# SCH_Display-LCD_Altium.net
KiCad netlist of a schematic drawn in Altium Designer
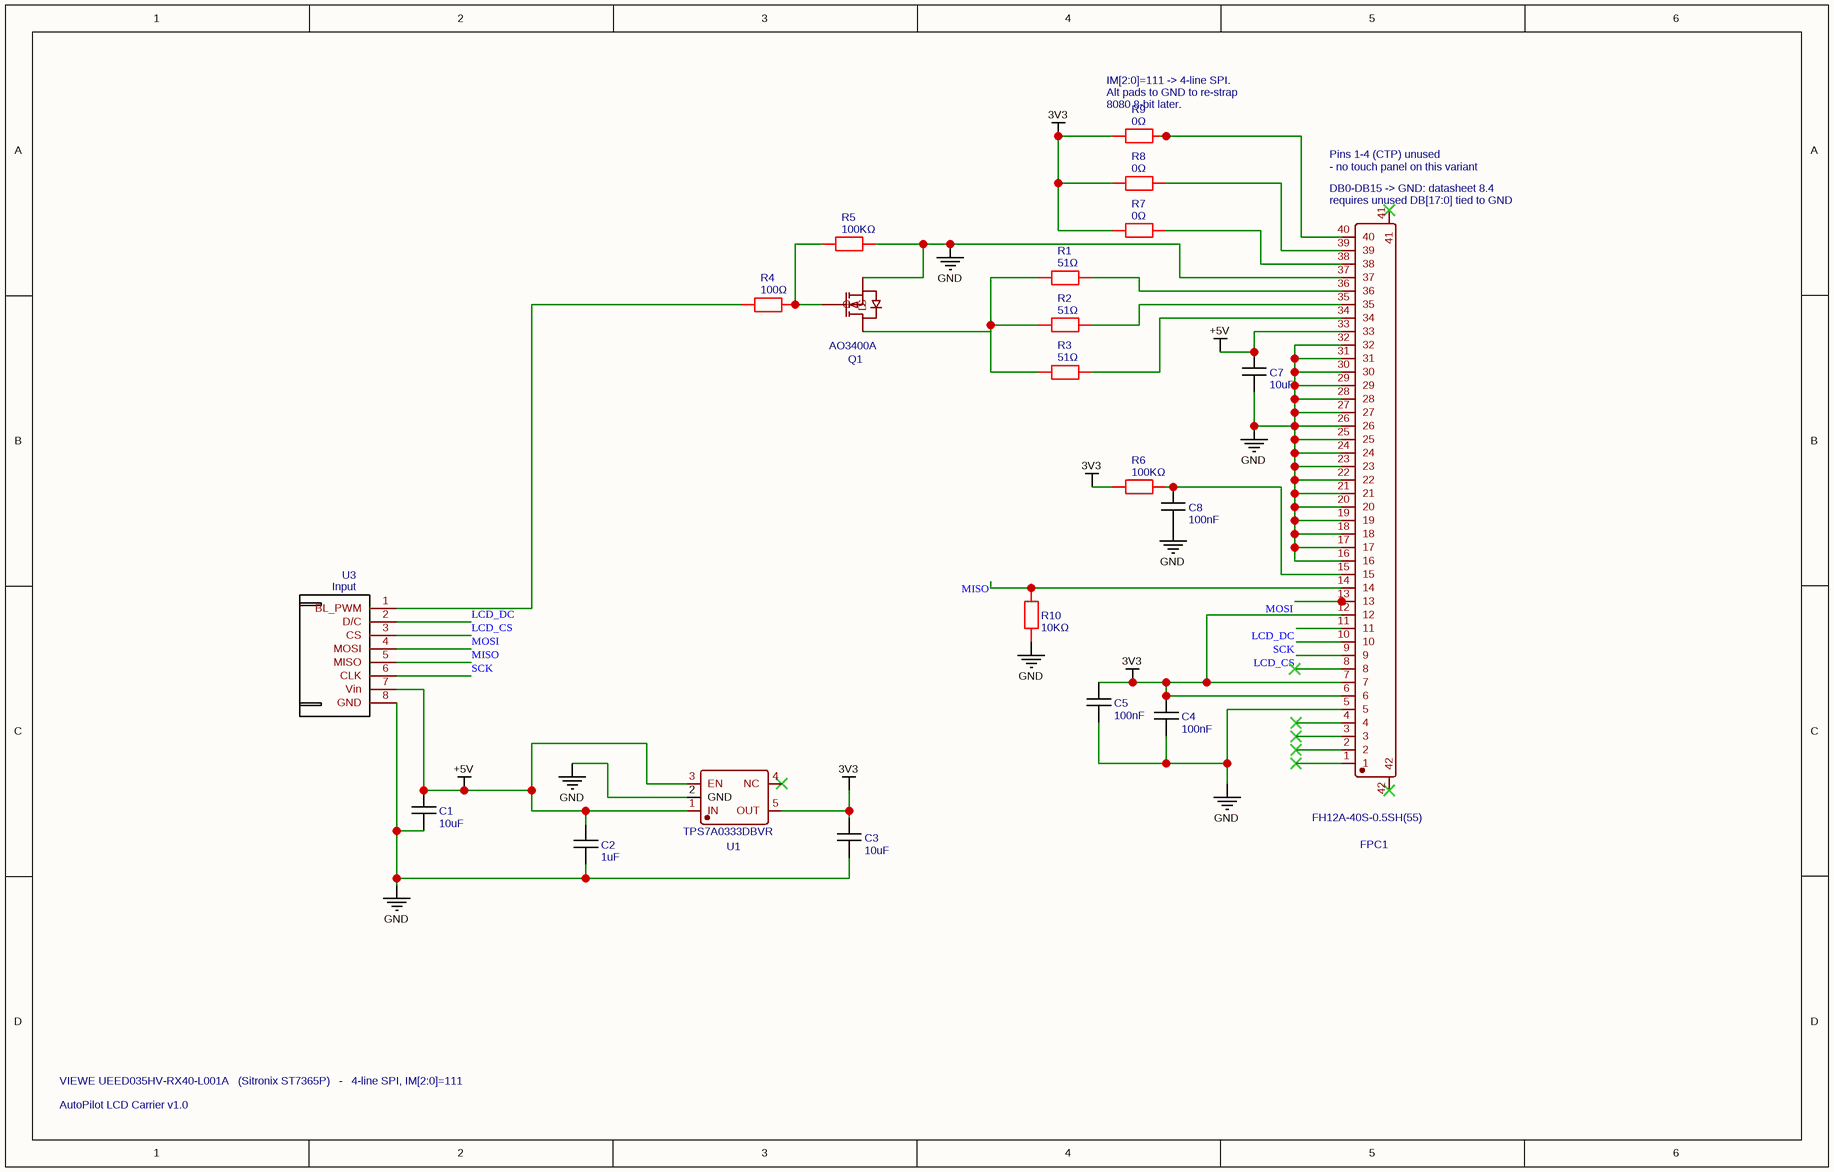
[diagram p0: SCH_Display-LCD_Altium.schdoc]

(export (version "E")
  (design (tool "Eeschema 10.0.6"))
  (components
    (comp (ref "C1")
      (value "10uF")
      (fields
        (field (name "MANUFACTURER PART") "Capacitor_Ceramic")
        (field (name "CONTRIBUTOR") "huuvinhz755")
      )
      (libsource (lib "altium-import") (part "root_3_10uF_"))
    )
    (comp (ref "C2")
      (value "1uF")
      (fields
        (field (name "MANUFACTURER PART") "Capacitor_Ceramic")
        (field (name "CONTRIBUTOR") "huuvinhz755")
      )
      (libsource (lib "altium-import") (part "root_3_1uF_"))
    )
    (comp (ref "C3")
      (value "10uF")
      (fields
        (field (name "MANUFACTURER PART") "Capacitor_Ceramic")
        (field (name "CONTRIBUTOR") "huuvinhz755")
      )
      (libsource (lib "altium-import") (part "root_3_10uF_"))
    )
    (comp (ref "C4")
      (value "100nF")
      (fields
        (field (name "MANUFACTURER PART") "Capacitor_Ceramic")
        (field (name "CONTRIBUTOR") "huuvinhz755")
      )
      (libsource (lib "altium-import") (part "root_3_100nF_"))
    )
    (comp (ref "C5")
      (value "100nF")
      (fields
        (field (name "MANUFACTURER PART") "Capacitor_Ceramic")
        (field (name "CONTRIBUTOR") "huuvinhz755")
      )
      (libsource (lib "altium-import") (part "root_3_100nF_"))
    )
    (comp (ref "C7")
      (value "10uF")
      (fields
        (field (name "MANUFACTURER PART") "Capacitor_Ceramic")
        (field (name "CONTRIBUTOR") "huuvinhz755")
      )
      (libsource (lib "altium-import") (part "root_3_10uF_"))
    )
    (comp (ref "C8")
      (value "100nF")
      (fields
        (field (name "MANUFACTURER PART") "Capacitor_Ceramic")
        (field (name "CONTRIBUTOR") "huuvinhz755")
      )
      (libsource (lib "altium-import") (part "root_3_100nF_"))
    )
    (comp (ref "FPC1")
      (value "FH12A-40S-0.5SH(55)")
      (fields (field (name "MANUFACTURER") "HRS(广濑)") (field (name "CONTRIBUTOR") "LCSC"))
      (libsource (lib "altium-import") (part "root_0_FH12A-40S-0.5SH(55)_"))
    )
    (comp (ref "Q1")
      (value "AO3400A")
      (fields (field (name "MANUFACTURER") "AOS"))
      (libsource (lib "altium-import") (part "root_0_AO3400A_"))
    )
    (comp (ref "R1")
      (value "51Ω")
      (fields (field (name "CONTRIBUTOR") "Kagutsuchi"))
      (libsource (lib "altium-import") (part "root_0_51Ω_"))
    )
    (comp (ref "R2")
      (value "51Ω")
      (fields (field (name "CONTRIBUTOR") "Kagutsuchi"))
      (libsource (lib "altium-import") (part "root_0_51Ω_"))
    )
    (comp (ref "R3")
      (value "51Ω")
      (fields (field (name "CONTRIBUTOR") "Kagutsuchi"))
      (libsource (lib "altium-import") (part "root_0_51Ω_"))
    )
    (comp (ref "R4")
      (value "100Ω")
      (fields (field (name "CONTRIBUTOR") "Kagutsuchi"))
      (libsource (lib "altium-import") (part "root_0_100Ω_"))
    )
    (comp (ref "R5")
      (value "100KΩ")
      (fields (field (name "CONTRIBUTOR") "Kagutsuchi"))
      (libsource (lib "altium-import") (part "root_0_100KΩ_"))
    )
    (comp (ref "R6")
      (value "100KΩ")
      (fields (field (name "CONTRIBUTOR") "Kagutsuchi"))
      (libsource (lib "altium-import") (part "root_0_100KΩ_"))
    )
    (comp (ref "R7")
      (value "0Ω")
      (fields (field (name "CONTRIBUTOR") "Kagutsuchi"))
      (libsource (lib "altium-import") (part "root_0_0Ω_"))
    )
    (comp (ref "R8")
      (value "0Ω")
      (fields (field (name "CONTRIBUTOR") "Kagutsuchi"))
      (libsource (lib "altium-import") (part "root_0_0Ω_"))
    )
    (comp (ref "R9")
      (value "0Ω")
      (fields (field (name "CONTRIBUTOR") "Kagutsuchi"))
      (libsource (lib "altium-import") (part "root_0_0Ω_"))
    )
    (comp (ref "R10")
      (value "10KΩ")
      (fields (field (name "CONTRIBUTOR") "Kagutsuchi"))
      (libsource (lib "altium-import") (part "root_3_10KΩ_"))
    )
    (comp (ref "U1")
      (value "TPS7A0333DBVR")
      (fields (field (name "MANUFACTURER") "TI(德州仪器)") (field (name "CONTRIBUTOR") "lcsc"))
      (libsource (lib "altium-import") (part "root_0_TPS7A0333DBVR_"))
    )
    (comp (ref "U3")
      (value "Input")
      (fields (field (name "CONTRIBUTOR") "loyboy"))
      (libsource (lib "altium-import") (part "root_0_Input_"))
    )
  )
  (nets
    (net (code "1") (name "+5V") (class "Default")
      (node (ref "C1") (pin "1") (pinfunction "1_1") (pintype "passive"))
      (node (ref "C2") (pin "1") (pinfunction "1_1") (pintype "passive"))
      (node (ref "C7") (pin "1") (pinfunction "1_1") (pintype "passive"))
      (node (ref "FPC1") (pin "33") (pinfunction "33_33") (pintype "passive"))
      (node (ref "U1") (pin "1") (pinfunction "IN_1") (pintype "passive"))
      (node (ref "U1") (pin "3") (pinfunction "EN_3") (pintype "passive"))
      (node (ref "U3") (pin "7") (pinfunction "Vin_7") (pintype "passive"))
    )
    (net (code "2") (name "/LCD_CS") (class "Default")
      (node (ref "FPC1") (pin "9") (pinfunction "9_9") (pintype "passive"))
      (node (ref "U3") (pin "3") (pinfunction "CS_3") (pintype "passive"))
    )
    (net (code "3") (name "/LCD_DC") (class "Default")
      (node (ref "FPC1") (pin "11") (pinfunction "11_11") (pintype "passive"))
      (node (ref "U3") (pin "2") (pinfunction "D/C_2") (pintype "passive"))
    )
    (net (code "4") (name "/MISO") (class "Default")
      (node (ref "FPC1") (pin "14") (pinfunction "14_14") (pintype "passive"))
      (node (ref "R10") (pin "1") (pinfunction "2_1") (pintype "passive"))
      (node (ref "U3") (pin "5") (pinfunction "MISO_5") (pintype "passive"))
    )
    (net (code "5") (name "/MOSI") (class "Default")
      (node (ref "FPC1") (pin "13") (pinfunction "13_13") (pintype "passive"))
      (node (ref "U3") (pin "4") (pinfunction "MOSI_4") (pintype "passive"))
    )
    (net (code "6") (name "/SCK") (class "Default")
      (node (ref "FPC1") (pin "10") (pinfunction "10_10") (pintype "passive"))
      (node (ref "U3") (pin "6") (pinfunction "CLK_6") (pintype "passive"))
    )
    (net (code "7") (name "3V3") (class "Default")
      (node (ref "C3") (pin "1") (pinfunction "1_1") (pintype "passive"))
      (node (ref "C4") (pin "1") (pinfunction "1_1") (pintype "passive"))
      (node (ref "C5") (pin "1") (pinfunction "1_1") (pintype "passive"))
      (node (ref "FPC1") (pin "12") (pinfunction "12_12") (pintype "passive"))
      (node (ref "FPC1") (pin "6") (pinfunction "6_6") (pintype "passive"))
      (node (ref "FPC1") (pin "7") (pinfunction "7_7") (pintype "passive"))
      (node (ref "R6") (pin "1") (pinfunction "2_1") (pintype "passive"))
      (node (ref "R7") (pin "1") (pinfunction "2_1") (pintype "passive"))
      (node (ref "R8") (pin "1") (pinfunction "2_1") (pintype "passive"))
      (node (ref "R9") (pin "1") (pinfunction "2_1") (pintype "passive"))
      (node (ref "U1") (pin "5") (pinfunction "OUT_5") (pintype "passive"))
    )
    (net (code "8") (name "GND") (class "Default")
      (node (ref "C1") (pin "2") (pinfunction "2_2") (pintype "passive"))
      (node (ref "C2") (pin "2") (pinfunction "2_2") (pintype "passive"))
      (node (ref "C3") (pin "2") (pinfunction "2_2") (pintype "passive"))
      (node (ref "C4") (pin "2") (pinfunction "2_2") (pintype "passive"))
      (node (ref "C5") (pin "2") (pinfunction "2_2") (pintype "passive"))
      (node (ref "C7") (pin "2") (pinfunction "2_2") (pintype "passive"))
      (node (ref "C8") (pin "2") (pinfunction "2_2") (pintype "passive"))
      (node (ref "FPC1") (pin "16") (pinfunction "16_16") (pintype "passive"))
      (node (ref "FPC1") (pin "17") (pinfunction "17_17") (pintype "passive"))
      (node (ref "FPC1") (pin "18") (pinfunction "18_18") (pintype "passive"))
      (node (ref "FPC1") (pin "19") (pinfunction "19_19") (pintype "passive"))
      (node (ref "FPC1") (pin "20") (pinfunction "20_20") (pintype "passive"))
      (node (ref "FPC1") (pin "21") (pinfunction "21_21") (pintype "passive"))
      (node (ref "FPC1") (pin "22") (pinfunction "22_22") (pintype "passive"))
      (node (ref "FPC1") (pin "23") (pinfunction "23_23") (pintype "passive"))
      (node (ref "FPC1") (pin "24") (pinfunction "24_24") (pintype "passive"))
      (node (ref "FPC1") (pin "25") (pinfunction "25_25") (pintype "passive"))
      (node (ref "FPC1") (pin "26") (pinfunction "26_26") (pintype "passive"))
      (node (ref "FPC1") (pin "27") (pinfunction "27_27") (pintype "passive"))
      (node (ref "FPC1") (pin "28") (pinfunction "28_28") (pintype "passive"))
      (node (ref "FPC1") (pin "29") (pinfunction "29_29") (pintype "passive"))
      (node (ref "FPC1") (pin "30") (pinfunction "30_30") (pintype "passive"))
      (node (ref "FPC1") (pin "31") (pinfunction "31_31") (pintype "passive"))
      (node (ref "FPC1") (pin "32") (pinfunction "32_32") (pintype "passive"))
      (node (ref "FPC1") (pin "37") (pinfunction "37_37") (pintype "passive"))
      (node (ref "FPC1") (pin "5") (pinfunction "5_5") (pintype "passive"))
      (node (ref "Q1") (pin "2") (pinfunction "S_2") (pintype "passive"))
      (node (ref "R10") (pin "2") (pinfunction "1_2") (pintype "passive"))
      (node (ref "R5") (pin "2") (pinfunction "1_2") (pintype "passive"))
      (node (ref "U1") (pin "2") (pinfunction "GND_2") (pintype "passive"))
      (node (ref "U3") (pin "8") (pinfunction "GND_8") (pintype "passive"))
    )
    (net (code "9") (name "Net-(Q1-D)") (class "Default")
      (node (ref "Q1") (pin "3") (pinfunction "D_3") (pintype "passive"))
      (node (ref "R1") (pin "1") (pinfunction "2_1") (pintype "passive"))
      (node (ref "R2") (pin "1") (pinfunction "2_1") (pintype "passive"))
      (node (ref "R3") (pin "1") (pinfunction "2_1") (pintype "passive"))
    )
    (net (code "10") (name "Net-(Q1-G)") (class "Default")
      (node (ref "Q1") (pin "1") (pinfunction "G_1") (pintype "passive"))
      (node (ref "R4") (pin "2") (pinfunction "1_2") (pintype "passive"))
      (node (ref "R5") (pin "1") (pinfunction "2_1") (pintype "passive"))
    )
    (net (code "11") (name "Net-(R1-1)") (class "Default")
      (node (ref "FPC1") (pin "36") (pinfunction "36_36") (pintype "passive"))
      (node (ref "R1") (pin "2") (pinfunction "1_2") (pintype "passive"))
    )
    (net (code "12") (name "Net-(R2-1)") (class "Default")
      (node (ref "FPC1") (pin "35") (pinfunction "35_35") (pintype "passive"))
      (node (ref "R2") (pin "2") (pinfunction "1_2") (pintype "passive"))
    )
    (net (code "13") (name "Net-(R3-1)") (class "Default")
      (node (ref "FPC1") (pin "34") (pinfunction "34_34") (pintype "passive"))
      (node (ref "R3") (pin "2") (pinfunction "1_2") (pintype "passive"))
    )
    (net (code "14") (name "Net-(R4-2)") (class "Default")
      (node (ref "R4") (pin "1") (pinfunction "2_1") (pintype "passive"))
      (node (ref "U3") (pin "1") (pinfunction "BL_PWM_1") (pintype "passive"))
    )
    (net (code "15") (name "Net-(R6-1)") (class "Default")
      (node (ref "C8") (pin "1") (pinfunction "1_1") (pintype "passive"))
      (node (ref "FPC1") (pin "15") (pinfunction "15_15") (pintype "passive"))
      (node (ref "R6") (pin "2") (pinfunction "1_2") (pintype "passive"))
    )
    (net (code "16") (name "Net-(R7-1)") (class "Default")
      (node (ref "FPC1") (pin "38") (pinfunction "38_38") (pintype "passive"))
      (node (ref "R7") (pin "2") (pinfunction "1_2") (pintype "passive"))
    )
    (net (code "17") (name "Net-(R8-1)") (class "Default")
      (node (ref "FPC1") (pin "39") (pinfunction "39_39") (pintype "passive"))
      (node (ref "R8") (pin "2") (pinfunction "1_2") (pintype "passive"))
    )
    (net (code "18") (name "Net-(R9-1)") (class "Default")
      (node (ref "FPC1") (pin "40") (pinfunction "40_40") (pintype "passive"))
      (node (ref "R9") (pin "2") (pinfunction "1_2") (pintype "passive"))
    )
    (net (code "19") (name "unconnected-(FPC1-Pad1)") (class "Default")
      (node (ref "FPC1") (pin "1") (pinfunction "1_1") (pintype "passive+no_connect"))
    )
    (net (code "20") (name "unconnected-(FPC1-Pad2)") (class "Default")
      (node (ref "FPC1") (pin "2") (pinfunction "2_2") (pintype "passive+no_connect"))
    )
    (net (code "21") (name "unconnected-(FPC1-Pad3)") (class "Default")
      (node (ref "FPC1") (pin "3") (pinfunction "3_3") (pintype "passive+no_connect"))
    )
    (net (code "22") (name "unconnected-(FPC1-Pad4)") (class "Default")
      (node (ref "FPC1") (pin "4") (pinfunction "4_4") (pintype "passive+no_connect"))
    )
    (net (code "23") (name "unconnected-(FPC1-Pad8)") (class "Default")
      (node (ref "FPC1") (pin "8") (pinfunction "8_8") (pintype "passive+no_connect"))
    )
    (net (code "24") (name "unconnected-(FPC1-Pad41)") (class "Default")
      (node (ref "FPC1") (pin "41") (pinfunction "41_41") (pintype "passive+no_connect"))
    )
    (net (code "25") (name "unconnected-(FPC1-Pad42)") (class "Default")
      (node (ref "FPC1") (pin "42") (pinfunction "42_42") (pintype "passive+no_connect"))
    )
    (net (code "26") (name "unconnected-(U1-NC-Pad4)") (class "Default")
      (node (ref "U1") (pin "4") (pinfunction "NC_4") (pintype "passive+no_connect"))
    )
  )
)
